# Lighting_Board.net
KiCad netlist of a schematic drawn in EAGLE
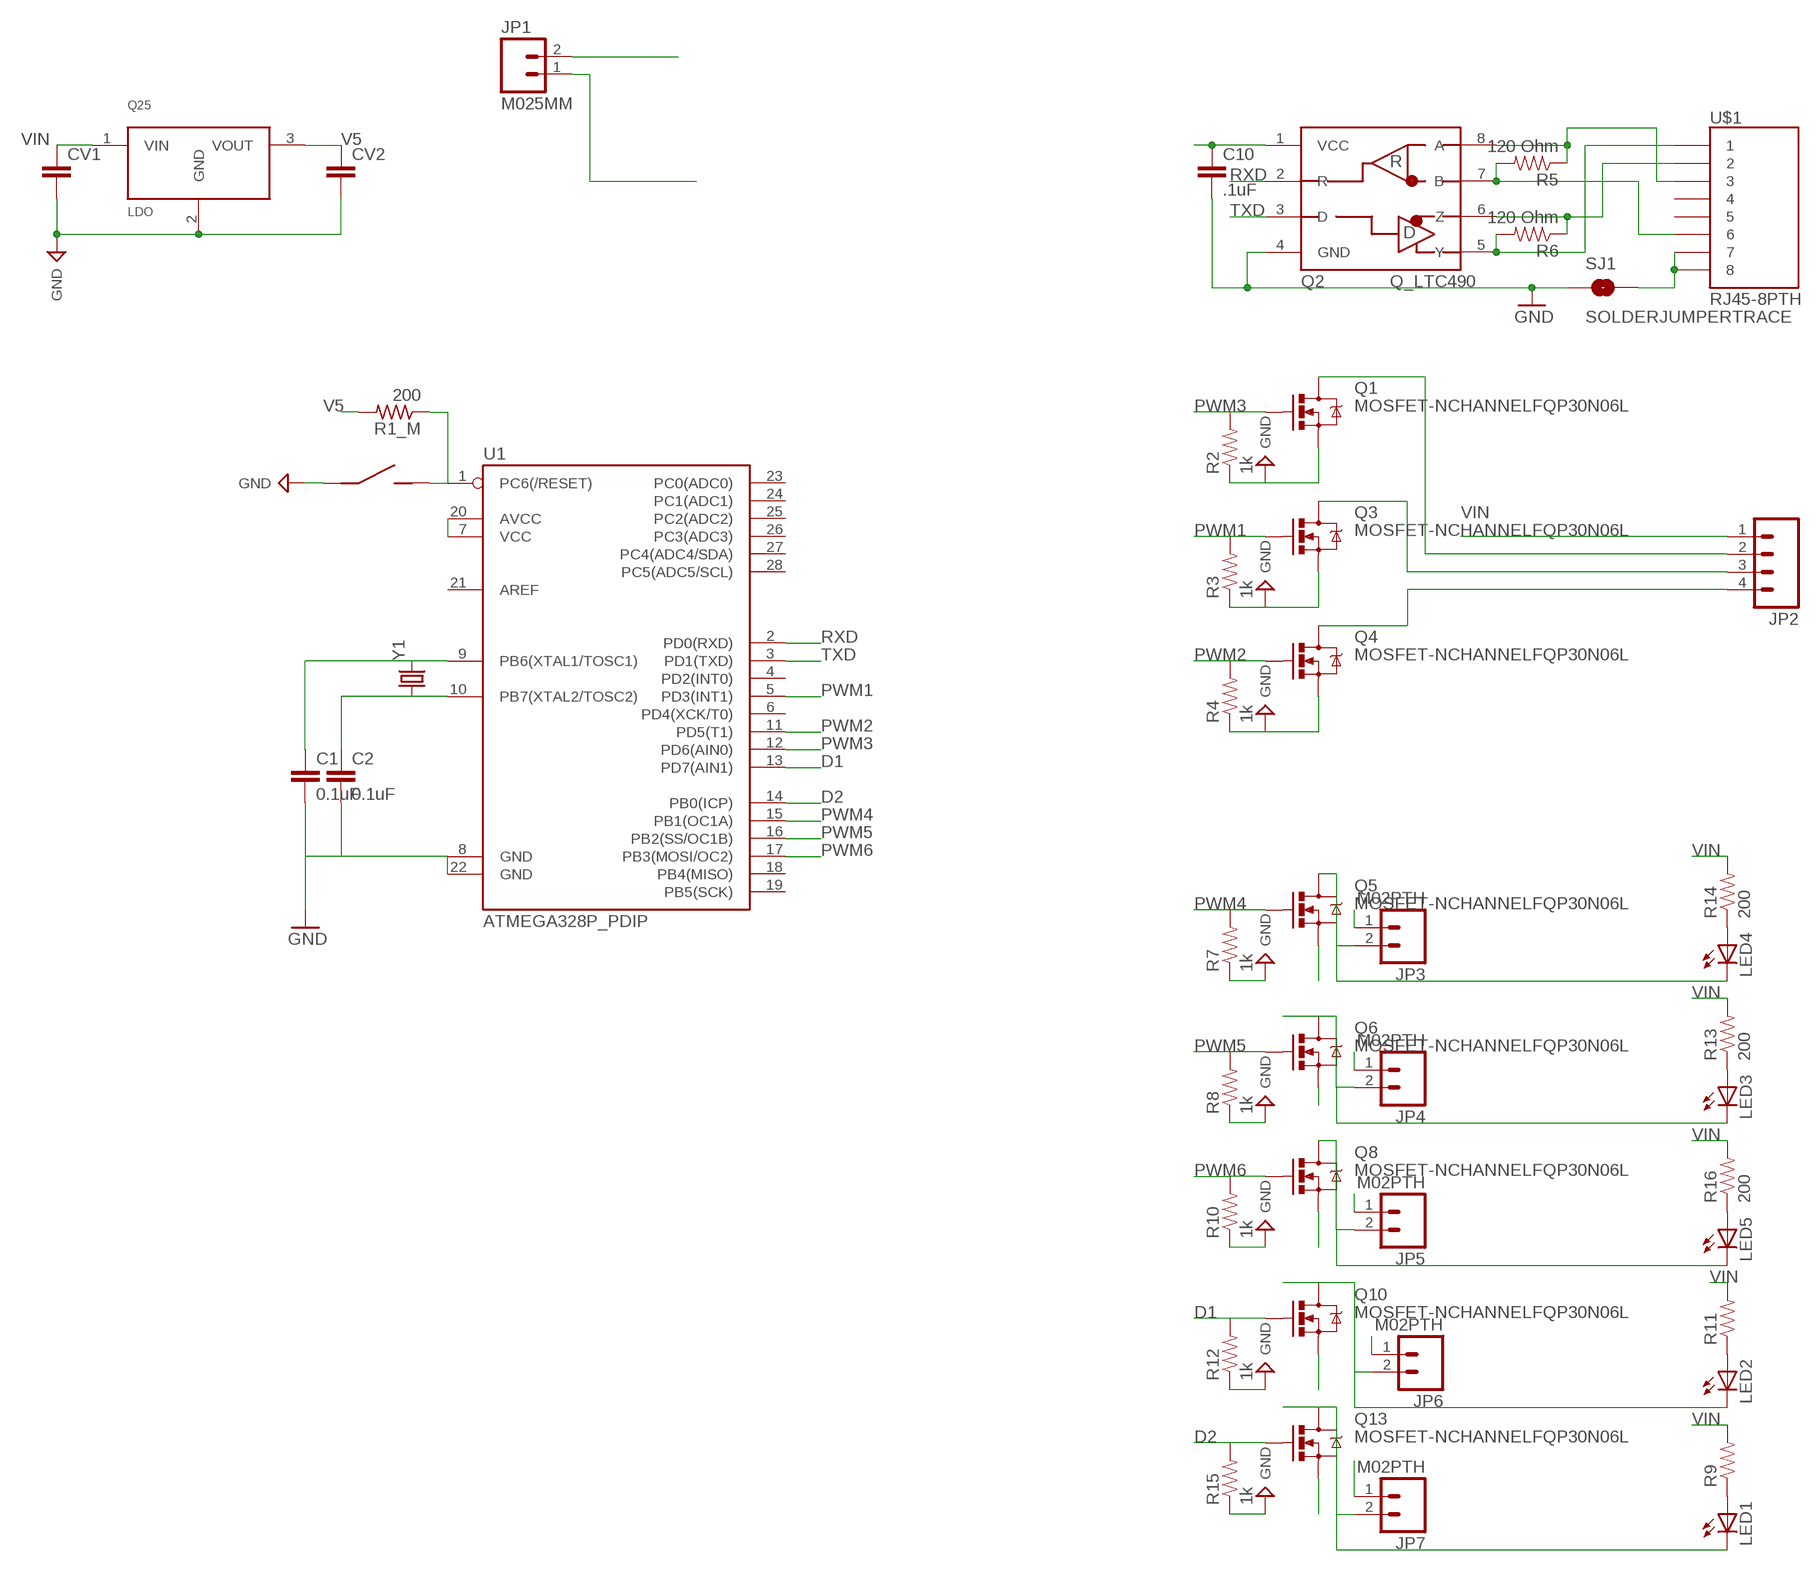
[diagram p0: schematic, sheet 1]

(export (version "E")
  (design (tool "Eeschema 10.0.6"))
  (components
    (comp (ref "C1")
      (value "0.1uF")
      (footprint "eagle-import:1206")
      (libsource (lib "eagle-import") (part "CAP1206"))
    )
    (comp (ref "C2")
      (value "0.1uF")
      (footprint "eagle-import:1206")
      (libsource (lib "eagle-import") (part "CAP1206"))
    )
    (comp (ref "C10")
      (value ".1uF")
      (footprint "eagle-import:1206")
      (libsource (lib "eagle-import") (part "2.2UF-CERCAP-10009"))
    )
    (comp (ref "CV1")
      (value "C_CAP_0805")
      (footprint "eagle-import:C_0805")
      (libsource (lib "eagle-import") (part "C_CAP_0805"))
    )
    (comp (ref "CV2")
      (value "C_CAP_0805")
      (footprint "eagle-import:C_0805")
      (libsource (lib "eagle-import") (part "C_CAP_0805"))
    )
    (comp (ref "JP1")
      (value "M025MM")
      (footprint "eagle-import:SCREWTERMINAL-5MM-2")
      (libsource (lib "eagle-import") (part "M025MM"))
    )
    (comp (ref "JP2")
      (value "M04PTH")
      (footprint "eagle-import:1X04")
      (libsource (lib "eagle-import") (part "M04PTH"))
    )
    (comp (ref "JP3")
      (value "M02PTH")
      (footprint "eagle-import:1X02")
      (libsource (lib "eagle-import") (part "M02PTH"))
    )
    (comp (ref "JP4")
      (value "M02PTH")
      (footprint "eagle-import:1X02")
      (libsource (lib "eagle-import") (part "M02PTH"))
    )
    (comp (ref "JP5")
      (value "M02PTH")
      (footprint "eagle-import:1X02")
      (libsource (lib "eagle-import") (part "M02PTH"))
    )
    (comp (ref "JP6")
      (value "M02PTH")
      (footprint "eagle-import:1X02")
      (libsource (lib "eagle-import") (part "M02PTH"))
    )
    (comp (ref "JP7")
      (value "M02PTH")
      (footprint "eagle-import:1X02")
      (libsource (lib "eagle-import") (part "M02PTH"))
    )
    (comp (ref "LED1")
      (value "LED1206")
      (footprint "eagle-import:LED-1206")
      (libsource (lib "eagle-import") (part "LED1206"))
    )
    (comp (ref "LED2")
      (value "LED1206")
      (footprint "eagle-import:LED-1206")
      (libsource (lib "eagle-import") (part "LED1206"))
    )
    (comp (ref "LED3")
      (value "LED1206")
      (footprint "eagle-import:LED-1206")
      (libsource (lib "eagle-import") (part "LED1206"))
    )
    (comp (ref "LED4")
      (value "LED1206")
      (footprint "eagle-import:LED-1206")
      (libsource (lib "eagle-import") (part "LED1206"))
    )
    (comp (ref "LED5")
      (value "LED1206")
      (footprint "eagle-import:LED-1206")
      (libsource (lib "eagle-import") (part "LED1206"))
    )
    (comp (ref "MS")
      (value "J_MC32857")
      (footprint "eagle-import:J_TOGGLE")
      (libsource (lib "eagle-import") (part "J_MC32857"))
    )
    (comp (ref "Q1")
      (value "MOSFET-NCHANNELFQP30N06L")
      (footprint "eagle-import:TO220V")
      (libsource (lib "eagle-import") (part "MOSFET-NCHANNELFQP30N06L"))
    )
    (comp (ref "Q2")
      (value "Q_LTC490")
      (footprint "eagle-import:DIP8")
      (libsource (lib "eagle-import") (part "Q_LTC490"))
    )
    (comp (ref "Q3")
      (value "MOSFET-NCHANNELFQP30N06L")
      (footprint "eagle-import:TO220V")
      (libsource (lib "eagle-import") (part "MOSFET-NCHANNELFQP30N06L"))
    )
    (comp (ref "Q4")
      (value "MOSFET-NCHANNELFQP30N06L")
      (footprint "eagle-import:TO220V")
      (libsource (lib "eagle-import") (part "MOSFET-NCHANNELFQP30N06L"))
    )
    (comp (ref "Q5")
      (value "MOSFET-NCHANNELFQP30N06L")
      (footprint "eagle-import:TO220V")
      (libsource (lib "eagle-import") (part "MOSFET-NCHANNELFQP30N06L"))
    )
    (comp (ref "Q6")
      (value "MOSFET-NCHANNELFQP30N06L")
      (footprint "eagle-import:TO220V")
      (libsource (lib "eagle-import") (part "MOSFET-NCHANNELFQP30N06L"))
    )
    (comp (ref "Q8")
      (value "MOSFET-NCHANNELFQP30N06L")
      (footprint "eagle-import:TO220V")
      (libsource (lib "eagle-import") (part "MOSFET-NCHANNELFQP30N06L"))
    )
    (comp (ref "Q10")
      (value "MOSFET-NCHANNELFQP30N06L")
      (footprint "eagle-import:TO220V")
      (libsource (lib "eagle-import") (part "MOSFET-NCHANNELFQP30N06L"))
    )
    (comp (ref "Q13")
      (value "MOSFET-NCHANNELFQP30N06L")
      (footprint "eagle-import:TO220V")
      (libsource (lib "eagle-import") (part "MOSFET-NCHANNELFQP30N06L"))
    )
    (comp (ref "Q25")
      (value "LDO")
      (footprint "eagle-import:TO-220")
      (libsource (lib "eagle-import") (part "Q_LDO"))
    )
    (comp (ref "R1_M")
      (value "200")
      (footprint "eagle-import:R_0805")
      (libsource (lib "eagle-import") (part "R_RES_0805"))
    )
    (comp (ref "R2")
      (value "1k")
      (footprint "eagle-import:1206")
      (libsource (lib "eagle-import") (part "RESISTOR1206"))
    )
    (comp (ref "R3")
      (value "1k")
      (footprint "eagle-import:1206")
      (libsource (lib "eagle-import") (part "RESISTOR1206"))
    )
    (comp (ref "R4")
      (value "1k")
      (footprint "eagle-import:1206")
      (libsource (lib "eagle-import") (part "RESISTOR1206"))
    )
    (comp (ref "R5")
      (value "120 Ohm")
      (footprint "eagle-import:1206")
      (libsource (lib "eagle-import") (part "RESISTOR1206"))
    )
    (comp (ref "R6")
      (value "120 Ohm")
      (footprint "eagle-import:1206")
      (libsource (lib "eagle-import") (part "RESISTOR1206"))
    )
    (comp (ref "R7")
      (value "1k")
      (footprint "eagle-import:1206")
      (libsource (lib "eagle-import") (part "RESISTOR1206"))
    )
    (comp (ref "R8")
      (value "1k")
      (footprint "eagle-import:1206")
      (libsource (lib "eagle-import") (part "RESISTOR1206"))
    )
    (comp (ref "R9")
      (value "RESISTOR1206")
      (footprint "eagle-import:1206")
      (libsource (lib "eagle-import") (part "RESISTOR1206"))
    )
    (comp (ref "R10")
      (value "1k")
      (footprint "eagle-import:1206")
      (libsource (lib "eagle-import") (part "RESISTOR1206"))
    )
    (comp (ref "R11")
      (value "RESISTOR1206")
      (footprint "eagle-import:1206")
      (libsource (lib "eagle-import") (part "RESISTOR1206"))
    )
    (comp (ref "R12")
      (value "1k")
      (footprint "eagle-import:1206")
      (libsource (lib "eagle-import") (part "RESISTOR1206"))
    )
    (comp (ref "R13")
      (value "200")
      (footprint "eagle-import:1206")
      (libsource (lib "eagle-import") (part "RESISTOR1206"))
    )
    (comp (ref "R14")
      (value "200")
      (footprint "eagle-import:1206")
      (libsource (lib "eagle-import") (part "RESISTOR1206"))
    )
    (comp (ref "R15")
      (value "1k")
      (footprint "eagle-import:1206")
      (libsource (lib "eagle-import") (part "RESISTOR1206"))
    )
    (comp (ref "R16")
      (value "200")
      (footprint "eagle-import:1206")
      (libsource (lib "eagle-import") (part "RESISTOR1206"))
    )
    (comp (ref "SJ1")
      (value "SOLDERJUMPERTRACE")
      (footprint "eagle-import:SJ_2S-TRACE")
      (libsource (lib "eagle-import") (part "SOLDERJUMPERTRACE"))
    )
    (comp (ref "U$1")
      (value "RJ45-8PTH")
      (footprint "eagle-import:RJ45-8")
      (libsource (lib "eagle-import") (part "RJ45-8PTH"))
    )
    (comp (ref "U1")
      (value "ATMEGA328P_PDIP")
      (footprint "eagle-import:DIL28-3")
      (libsource (lib "eagle-import") (part "ATMEGA328P_PDIP"))
    )
    (comp (ref "Y1")
      (value "CRYSTALHC49US")
      (footprint "eagle-import:HC49US")
      (libsource (lib "eagle-import") (part "CRYSTALHC49US"))
    )
  )
  (nets
    (net (code "1") (name "/D1") (class "Default")
      (node (ref "Q10") (pin "1") (pinfunction "G_1") (pintype "passive"))
      (node (ref "R12") (pin "2") (pinfunction "2_2") (pintype "passive"))
      (node (ref "U1") (pin "13") (pinfunction "PD7(AIN1)_13") (pintype "bidirectional"))
    )
    (net (code "2") (name "/D2") (class "Default")
      (node (ref "Q13") (pin "1") (pinfunction "G_1") (pintype "passive"))
      (node (ref "R15") (pin "2") (pinfunction "2_2") (pintype "passive"))
      (node (ref "U1") (pin "14") (pinfunction "PB0(ICP)_14") (pintype "bidirectional"))
    )
    (net (code "3") (name "/PWM1") (class "Default")
      (node (ref "Q3") (pin "1") (pinfunction "G_1") (pintype "passive"))
      (node (ref "R3") (pin "2") (pinfunction "2_2") (pintype "passive"))
      (node (ref "U1") (pin "5") (pinfunction "PD3(INT1)_5") (pintype "bidirectional"))
    )
    (net (code "4") (name "/PWM2") (class "Default")
      (node (ref "Q4") (pin "1") (pinfunction "G_1") (pintype "passive"))
      (node (ref "R4") (pin "2") (pinfunction "2_2") (pintype "passive"))
      (node (ref "U1") (pin "11") (pinfunction "PD5(T1)_11") (pintype "bidirectional"))
    )
    (net (code "5") (name "/PWM3") (class "Default")
      (node (ref "Q1") (pin "1") (pinfunction "G_1") (pintype "passive"))
      (node (ref "R2") (pin "2") (pinfunction "2_2") (pintype "passive"))
      (node (ref "U1") (pin "12") (pinfunction "PD6(AIN0)_12") (pintype "bidirectional"))
    )
    (net (code "6") (name "/PWM4") (class "Default")
      (node (ref "Q5") (pin "1") (pinfunction "G_1") (pintype "passive"))
      (node (ref "R7") (pin "2") (pinfunction "2_2") (pintype "passive"))
      (node (ref "U1") (pin "15") (pinfunction "PB1(OC1A)_15") (pintype "bidirectional"))
    )
    (net (code "7") (name "/PWM5") (class "Default")
      (node (ref "Q6") (pin "1") (pinfunction "G_1") (pintype "passive"))
      (node (ref "R8") (pin "2") (pinfunction "2_2") (pintype "passive"))
      (node (ref "U1") (pin "16") (pinfunction "PB2(SS/OC1B)_16") (pintype "bidirectional"))
    )
    (net (code "8") (name "/PWM6") (class "Default")
      (node (ref "Q8") (pin "1") (pinfunction "G_1") (pintype "passive"))
      (node (ref "R10") (pin "2") (pinfunction "2_2") (pintype "passive"))
      (node (ref "U1") (pin "17") (pinfunction "PB3(MOSI/OC2)_17") (pintype "bidirectional"))
    )
    (net (code "9") (name "/RXD") (class "Default")
      (node (ref "Q2") (pin "2") (pinfunction "R_2") (pintype "bidirectional"))
      (node (ref "U1") (pin "2") (pinfunction "PD0(RXD)_2") (pintype "bidirectional"))
    )
    (net (code "10") (name "/TXD") (class "Default")
      (node (ref "Q2") (pin "3") (pinfunction "D_3") (pintype "bidirectional"))
      (node (ref "U1") (pin "3") (pinfunction "PD1(TXD)_3") (pintype "bidirectional"))
    )
    (net (code "11") (name "/V5") (class "Default")
      (node (ref "C10") (pin "1") (pinfunction "1_1") (pintype "passive"))
      (node (ref "CV2") (pin "1") (pinfunction "1_1") (pintype "passive"))
      (node (ref "Q2") (pin "1") (pinfunction "VCC_1") (pintype "bidirectional"))
      (node (ref "Q25") (pin "3") (pinfunction "VOUT_3") (pintype "bidirectional"))
      (node (ref "R1_M") (pin "2") (pinfunction "2_2") (pintype "passive"))
      (node (ref "U1") (pin "20") (pinfunction "AVCC_20") (pintype "bidirectional"))
      (node (ref "U1") (pin "7") (pinfunction "VCC_7") (pintype "bidirectional"))
    )
    (net (code "12") (name "/VIN") (class "Default")
      (node (ref "CV1") (pin "1") (pinfunction "1_1") (pintype "passive"))
      (node (ref "JP1") (pin "1") (pinfunction "1_1") (pintype "passive"))
      (node (ref "JP2") (pin "1") (pinfunction "1_1") (pintype "passive"))
      (node (ref "JP3") (pin "1") (pinfunction "1_1") (pintype "passive"))
      (node (ref "JP4") (pin "1") (pinfunction "1_1") (pintype "passive"))
      (node (ref "JP5") (pin "1") (pinfunction "1_1") (pintype "passive"))
      (node (ref "JP6") (pin "1") (pinfunction "1_1") (pintype "passive"))
      (node (ref "JP7") (pin "1") (pinfunction "1_1") (pintype "passive"))
      (node (ref "Q25") (pin "1") (pinfunction "VIN_1") (pintype "bidirectional"))
      (node (ref "R11") (pin "2") (pinfunction "2_2") (pintype "passive"))
      (node (ref "R13") (pin "2") (pinfunction "2_2") (pintype "passive"))
      (node (ref "R14") (pin "2") (pinfunction "2_2") (pintype "passive"))
      (node (ref "R16") (pin "2") (pinfunction "2_2") (pintype "passive"))
      (node (ref "R9") (pin "2") (pinfunction "2_2") (pintype "passive"))
    )
    (net (code "13") (name "GND") (class "Default")
      (node (ref "C1") (pin "2") (pinfunction "2_2") (pintype "passive"))
      (node (ref "C10") (pin "2") (pinfunction "2_2") (pintype "passive"))
      (node (ref "C2") (pin "2") (pinfunction "2_2") (pintype "passive"))
      (node (ref "CV1") (pin "2") (pinfunction "2_2") (pintype "passive"))
      (node (ref "CV2") (pin "2") (pinfunction "2_2") (pintype "passive"))
      (node (ref "JP1") (pin "2") (pinfunction "2_2") (pintype "passive"))
      (node (ref "MS") (pin "P$1") (pinfunction "1_P$1") (pintype "bidirectional"))
      (node (ref "Q1") (pin "3") (pinfunction "S_3") (pintype "passive"))
      (node (ref "Q10") (pin "3") (pinfunction "S_3") (pintype "passive"))
      (node (ref "Q13") (pin "3") (pinfunction "S_3") (pintype "passive"))
      (node (ref "Q2") (pin "4") (pinfunction "GND_4") (pintype "bidirectional"))
      (node (ref "Q25") (pin "2") (pinfunction "GND_2") (pintype "bidirectional"))
      (node (ref "Q3") (pin "3") (pinfunction "S_3") (pintype "passive"))
      (node (ref "Q4") (pin "3") (pinfunction "S_3") (pintype "passive"))
      (node (ref "Q5") (pin "3") (pinfunction "S_3") (pintype "passive"))
      (node (ref "Q6") (pin "3") (pinfunction "S_3") (pintype "passive"))
      (node (ref "Q8") (pin "3") (pinfunction "S_3") (pintype "passive"))
      (node (ref "R10") (pin "1") (pinfunction "1_1") (pintype "passive"))
      (node (ref "R12") (pin "1") (pinfunction "1_1") (pintype "passive"))
      (node (ref "R15") (pin "1") (pinfunction "1_1") (pintype "passive"))
      (node (ref "R2") (pin "1") (pinfunction "1_1") (pintype "passive"))
      (node (ref "R3") (pin "1") (pinfunction "1_1") (pintype "passive"))
      (node (ref "R4") (pin "1") (pinfunction "1_1") (pintype "passive"))
      (node (ref "R7") (pin "1") (pinfunction "1_1") (pintype "passive"))
      (node (ref "R8") (pin "1") (pinfunction "1_1") (pintype "passive"))
      (node (ref "SJ1") (pin "1") (pinfunction "1_1") (pintype "passive"))
      (node (ref "U1") (pin "22") (pinfunction "GND_22") (pintype "bidirectional"))
      (node (ref "U1") (pin "8") (pinfunction "GND_8") (pintype "bidirectional"))
    )
    (net (code "14") (name "Net-(LED1-PadA)") (class "Default")
      (node (ref "LED1") (pin "A") (pinfunction "A_A") (pintype "passive"))
      (node (ref "R9") (pin "1") (pinfunction "1_1") (pintype "passive"))
    )
    (net (code "15") (name "Net-(LED2-PadA)") (class "Default")
      (node (ref "LED2") (pin "A") (pinfunction "A_A") (pintype "passive"))
      (node (ref "R11") (pin "1") (pinfunction "1_1") (pintype "passive"))
    )
    (net (code "16") (name "Net-(LED3-PadA)") (class "Default")
      (node (ref "LED3") (pin "A") (pinfunction "A_A") (pintype "passive"))
      (node (ref "R13") (pin "1") (pinfunction "1_1") (pintype "passive"))
    )
    (net (code "17") (name "Net-(LED4-PadA)") (class "Default")
      (node (ref "LED4") (pin "A") (pinfunction "A_A") (pintype "passive"))
      (node (ref "R14") (pin "1") (pinfunction "1_1") (pintype "passive"))
    )
    (net (code "18") (name "Net-(LED5-PadA)") (class "Default")
      (node (ref "LED5") (pin "A") (pinfunction "A_A") (pintype "passive"))
      (node (ref "R16") (pin "1") (pinfunction "1_1") (pintype "passive"))
    )
    (net (code "19") (name "Net-(MS-2)") (class "Default")
      (node (ref "MS") (pin "P$2") (pinfunction "2_P$2") (pintype "bidirectional"))
      (node (ref "R1_M") (pin "1") (pinfunction "1_1") (pintype "passive"))
      (node (ref "U1") (pin "1") (pinfunction "PC6(/RESET)_1") (pintype "bidirectional"))
    )
    (net (code "20") (name "Net-(Q1-D)") (class "Default")
      (node (ref "JP2") (pin "2") (pinfunction "2_2") (pintype "passive"))
      (node (ref "Q1") (pin "2") (pinfunction "D_2") (pintype "passive"))
    )
    (net (code "21") (name "Net-(Q2-A)") (class "Default")
      (node (ref "Q2") (pin "8") (pinfunction "A_8") (pintype "bidirectional"))
      (node (ref "R5") (pin "1") (pinfunction "1_1") (pintype "passive"))
      (node (ref "U$1") (pin "3") (pinfunction "3_3") (pintype "bidirectional"))
    )
    (net (code "22") (name "Net-(Q2-B)") (class "Default")
      (node (ref "Q2") (pin "7") (pinfunction "B_7") (pintype "bidirectional"))
      (node (ref "R5") (pin "2") (pinfunction "2_2") (pintype "passive"))
      (node (ref "U$1") (pin "6") (pinfunction "6_6") (pintype "bidirectional"))
    )
    (net (code "23") (name "Net-(Q2-Y)") (class "Default")
      (node (ref "Q2") (pin "5") (pinfunction "Y_5") (pintype "bidirectional"))
      (node (ref "R6") (pin "2") (pinfunction "2_2") (pintype "passive"))
      (node (ref "U$1") (pin "1") (pinfunction "1_1") (pintype "bidirectional"))
    )
    (net (code "24") (name "Net-(Q2-Z)") (class "Default")
      (node (ref "Q2") (pin "6") (pinfunction "Z_6") (pintype "bidirectional"))
      (node (ref "R6") (pin "1") (pinfunction "1_1") (pintype "passive"))
      (node (ref "U$1") (pin "2") (pinfunction "2_2") (pintype "bidirectional"))
    )
    (net (code "25") (name "Net-(Q3-D)") (class "Default")
      (node (ref "JP2") (pin "3") (pinfunction "3_3") (pintype "passive"))
      (node (ref "Q3") (pin "2") (pinfunction "D_2") (pintype "passive"))
    )
    (net (code "26") (name "Net-(Q4-D)") (class "Default")
      (node (ref "JP2") (pin "4") (pinfunction "4_4") (pintype "passive"))
      (node (ref "Q4") (pin "2") (pinfunction "D_2") (pintype "passive"))
    )
    (net (code "27") (name "Net-(Q5-D)") (class "Default")
      (node (ref "JP3") (pin "2") (pinfunction "2_2") (pintype "passive"))
      (node (ref "LED4") (pin "C") (pinfunction "C_C") (pintype "passive"))
      (node (ref "Q5") (pin "2") (pinfunction "D_2") (pintype "passive"))
    )
    (net (code "28") (name "Net-(Q6-D)") (class "Default")
      (node (ref "JP4") (pin "2") (pinfunction "2_2") (pintype "passive"))
      (node (ref "LED3") (pin "C") (pinfunction "C_C") (pintype "passive"))
      (node (ref "Q6") (pin "2") (pinfunction "D_2") (pintype "passive"))
    )
    (net (code "29") (name "Net-(Q8-D)") (class "Default")
      (node (ref "JP5") (pin "2") (pinfunction "2_2") (pintype "passive"))
      (node (ref "LED5") (pin "C") (pinfunction "C_C") (pintype "passive"))
      (node (ref "Q8") (pin "2") (pinfunction "D_2") (pintype "passive"))
    )
    (net (code "30") (name "Net-(Q10-D)") (class "Default")
      (node (ref "JP6") (pin "2") (pinfunction "2_2") (pintype "passive"))
      (node (ref "LED2") (pin "C") (pinfunction "C_C") (pintype "passive"))
      (node (ref "Q10") (pin "2") (pinfunction "D_2") (pintype "passive"))
    )
    (net (code "31") (name "Net-(Q13-D)") (class "Default")
      (node (ref "JP7") (pin "2") (pinfunction "2_2") (pintype "passive"))
      (node (ref "LED1") (pin "C") (pinfunction "C_C") (pintype "passive"))
      (node (ref "Q13") (pin "2") (pinfunction "D_2") (pintype "passive"))
    )
    (net (code "32") (name "Net-(SJ1-Pad2)") (class "Default")
      (node (ref "SJ1") (pin "2") (pinfunction "2_2") (pintype "passive"))
      (node (ref "U$1") (pin "7") (pinfunction "7_7") (pintype "bidirectional"))
      (node (ref "U$1") (pin "8") (pinfunction "8_8") (pintype "bidirectional"))
    )
    (net (code "33") (name "Net-(U1-PB6(XTAL1{slash}TOSC1))") (class "Default")
      (node (ref "C1") (pin "1") (pinfunction "1_1") (pintype "passive"))
      (node (ref "U1") (pin "9") (pinfunction "PB6(XTAL1/TOSC1)_9") (pintype "bidirectional"))
      (node (ref "Y1") (pin "2") (pinfunction "2_2") (pintype "passive"))
    )
    (net (code "34") (name "Net-(U1-PB7(XTAL2{slash}TOSC2))") (class "Default")
      (node (ref "C2") (pin "1") (pinfunction "1_1") (pintype "passive"))
      (node (ref "U1") (pin "10") (pinfunction "PB7(XTAL2/TOSC2)_10") (pintype "bidirectional"))
      (node (ref "Y1") (pin "1") (pinfunction "1_1") (pintype "passive"))
    )
    (net (code "35") (name "unconnected-(U$1-Pad4)") (class "Default")
      (node (ref "U$1") (pin "4") (pinfunction "4_4") (pintype "bidirectional"))
    )
    (net (code "36") (name "unconnected-(U$1-Pad5)") (class "Default")
      (node (ref "U$1") (pin "5") (pinfunction "5_5") (pintype "bidirectional"))
    )
    (net (code "37") (name "unconnected-(U1-AREF-Pad21)") (class "Default")
      (node (ref "U1") (pin "21") (pinfunction "AREF_21") (pintype "bidirectional"))
    )
    (net (code "38") (name "unconnected-(U1-PB4(MISO)-Pad18)") (class "Default")
      (node (ref "U1") (pin "18") (pinfunction "PB4(MISO)_18") (pintype "bidirectional"))
    )
    (net (code "39") (name "unconnected-(U1-PB5(SCK)-Pad19)") (class "Default")
      (node (ref "U1") (pin "19") (pinfunction "PB5(SCK)_19") (pintype "bidirectional"))
    )
    (net (code "40") (name "unconnected-(U1-PC0(ADC0)-Pad23)") (class "Default")
      (node (ref "U1") (pin "23") (pinfunction "PC0(ADC0)_23") (pintype "bidirectional"))
    )
    (net (code "41") (name "unconnected-(U1-PC1(ADC1)-Pad24)") (class "Default")
      (node (ref "U1") (pin "24") (pinfunction "PC1(ADC1)_24") (pintype "bidirectional"))
    )
    (net (code "42") (name "unconnected-(U1-PC2(ADC2)-Pad25)") (class "Default")
      (node (ref "U1") (pin "25") (pinfunction "PC2(ADC2)_25") (pintype "bidirectional"))
    )
    (net (code "43") (name "unconnected-(U1-PC3(ADC3)-Pad26)") (class "Default")
      (node (ref "U1") (pin "26") (pinfunction "PC3(ADC3)_26") (pintype "bidirectional"))
    )
    (net (code "44") (name "unconnected-(U1-PC4(ADC4{slash}SDA)-Pad27)") (class "Default")
      (node (ref "U1") (pin "27") (pinfunction "PC4(ADC4/SDA)_27") (pintype "bidirectional"))
    )
    (net (code "45") (name "unconnected-(U1-PC5(ADC5{slash}SCL)-Pad28)") (class "Default")
      (node (ref "U1") (pin "28") (pinfunction "PC5(ADC5/SCL)_28") (pintype "bidirectional"))
    )
    (net (code "46") (name "unconnected-(U1-PD2(INT0)-Pad4)") (class "Default")
      (node (ref "U1") (pin "4") (pinfunction "PD2(INT0)_4") (pintype "bidirectional"))
    )
    (net (code "47") (name "unconnected-(U1-PD4(XCK{slash}T0)-Pad6)") (class "Default")
      (node (ref "U1") (pin "6") (pinfunction "PD4(XCK/T0)_6") (pintype "bidirectional"))
    )
  )
)
